# powersupply.net
KiCad netlist of a schematic drawn in Altium Designer
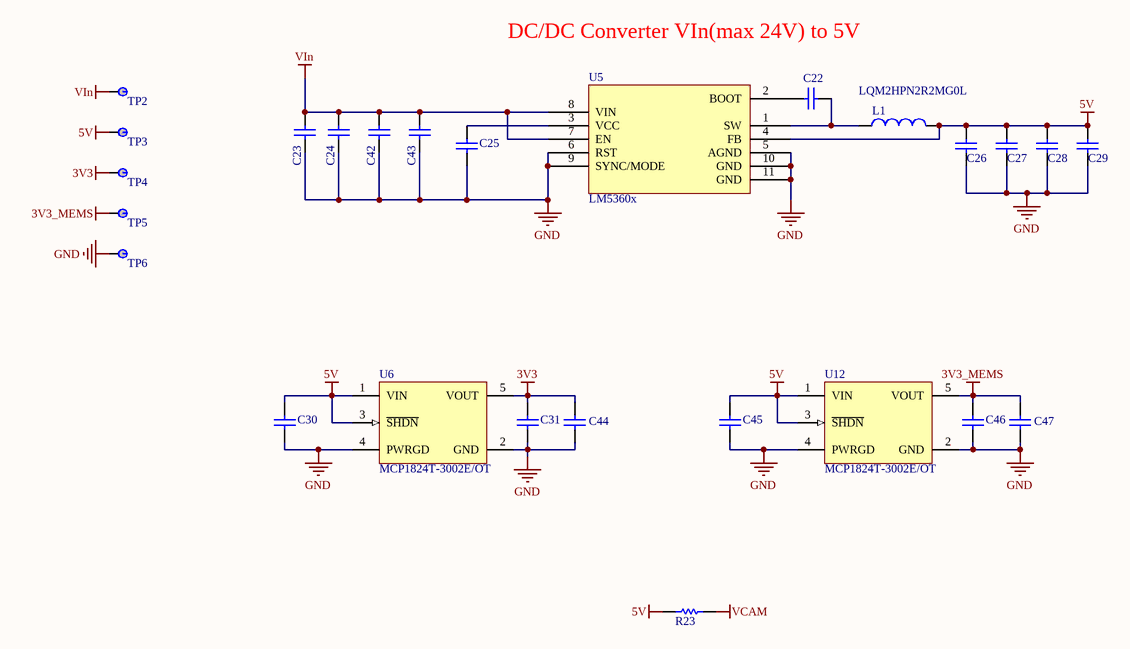
[diagram p0: powersupply.SchDoc]

(export (version "E")
  (design (tool "Eeschema 10.0.6"))
  (components
    (comp (ref "C22")
      (value "CAP 100nF 50V 0805(2012)")
      (footprint "CAPC0805(2012)100_M")
      (description "CAP 100nF 50V ±10% 0805 (2012 Metric) Thickness 1mm SMD")
      (fields (field (name "TOLERANCE") "Â±10%"))
      (libsource (lib "Altium Content Vault") (part "CAP"))
    )
    (comp (ref "C23")
      (value "CAP 4.7uF 50V 0805(2012)")
      (footprint "CAPC0805(2012)145_M")
      (description "CAP 4.7uF 50V ±20% 0805 (2012 Metric) Thickness 1.45mm SMD")
      (fields (field (name "TOLERANCE") "Â±20%"))
      (libsource (lib "Altium Content Vault") (part "CAP"))
    )
    (comp (ref "C24")
      (value "CAP 100nF 50V 0805(2012)")
      (footprint "CAPC0805(2012)100_M")
      (description "CAP 100nF 50V ±10% 0805 (2012 Metric) Thickness 1mm SMD")
      (fields (field (name "TOLERANCE") "Â±10%"))
      (libsource (lib "Altium Content Vault") (part "CAP"))
    )
    (comp (ref "C25")
      (value "CAP 1uF 6.3V 0603(1608)")
      (footprint "CAPC0603(1608)100_N")
      (description "CAP 1uF 6.3V ±10% 0603 (1608 Metric) Thickness 1mm SMD")
      (fields (field (name "TOLERANCE") "Â±10%"))
      (libsource (lib "Altium Content Vault") (part "CAP"))
    )
    (comp (ref "C26")
      (value "CAP 4.7uF 16V 0603(1608)")
      (footprint "CAPC0603(1608)100_N")
      (description "CAP 4.7uF 16V ±20% 0603 (1608 Metric) Thickness 1mm SMD")
      (fields (field (name "TOLERANCE") "Â±20%"))
      (libsource (lib "Altium Content Vault") (part "CAP"))
    )
    (comp (ref "C27")
      (value "CAP 4.7uF 16V 0603(1608)")
      (footprint "CAPC0603(1608)100_N")
      (description "CAP 4.7uF 16V ±20% 0603 (1608 Metric) Thickness 1mm SMD")
      (fields (field (name "TOLERANCE") "Â±20%"))
      (libsource (lib "Altium Content Vault") (part "CAP"))
    )
    (comp (ref "C28")
      (value "CAP 4.7uF 16V 0603(1608)")
      (footprint "CAPC0603(1608)100_N")
      (description "CAP 4.7uF 16V ±20% 0603 (1608 Metric) Thickness 1mm SMD")
      (fields (field (name "TOLERANCE") "Â±20%"))
      (libsource (lib "Altium Content Vault") (part "CAP"))
    )
    (comp (ref "C29")
      (value "CAP 4.7uF 16V 0603(1608)")
      (footprint "CAPC0603(1608)100_N")
      (description "CAP 4.7uF 16V ±20% 0603 (1608 Metric) Thickness 1mm SMD")
      (fields (field (name "TOLERANCE") "Â±20%"))
      (libsource (lib "Altium Content Vault") (part "CAP"))
    )
    (comp (ref "C30")
      (value "CAP 1uF 35V 0603(1608)")
      (footprint "CAPC0603(1608)100_L")
      (description "CAP 1uF 35V ±10% 0603 (1608 Metric) Thickness 1mm SMD")
      (fields (field (name "TOLERANCE") "Â±10%"))
      (libsource (lib "Altium Content Vault") (part "CAP"))
    )
    (comp (ref "C31")
      (value "CAP 1uF 35V 0603(1608)")
      (footprint "CAPC0603(1608)100_L")
      (description "CAP 1uF 35V ±10% 0603 (1608 Metric) Thickness 1mm SMD")
      (fields (field (name "TOLERANCE") "Â±10%"))
      (libsource (lib "Altium Content Vault") (part "CAP"))
    )
    (comp (ref "C42")
      (value "CAP 4.7uF 50V 1210(3225)")
      (footprint "CAPC1210(3225)280_L")
      (description "CAP 4.7uF 50V ±10% 1210 (3225 Metric) Thickness 2.8mm SMD")
      (fields (field (name "TOLERANCE") "Â±10%"))
      (libsource (lib "Altium Content Vault") (part "CAP"))
    )
    (comp (ref "C43")
      (value "CAP 4.7uF 50V 1210(3225)")
      (footprint "CAPC1210(3225)280_L")
      (description "CAP 4.7uF 50V ±10% 1210 (3225 Metric) Thickness 2.8mm SMD")
      (fields (field (name "TOLERANCE") "Â±10%"))
      (libsource (lib "Altium Content Vault") (part "CAP"))
    )
    (comp (ref "C44")
      (value "CAP 4.7uF 16V 0603(1608)")
      (footprint "CAPC0603(1608)100_L")
      (description "CAP 4.7uF 16V ±20% 0603 (1608 Metric) Thickness 1mm SMD")
      (fields (field (name "TOLERANCE") "Â±20%"))
      (libsource (lib "Altium Content Vault") (part "CMP-1035-02789-1"))
    )
    (comp (ref "C45")
      (value "CAP 1uF 35V 0603(1608)")
      (footprint "CAPC0603(1608)100_L")
      (description "CAP 1uF 35V ±10% 0603 (1608 Metric) Thickness 1mm SMD")
      (fields (field (name "TOLERANCE") "Â±10%"))
      (libsource (lib "Altium Content Vault") (part "CMP-1035-02743-1"))
    )
    (comp (ref "C46")
      (value "CAP 1uF 35V 0603(1608)")
      (footprint "CAPC0603(1608)100_L")
      (description "CAP 1uF 35V ±10% 0603 (1608 Metric) Thickness 1mm SMD")
      (fields (field (name "TOLERANCE") "Â±10%"))
      (libsource (lib "Altium Content Vault") (part "CMP-1035-02743-1"))
    )
    (comp (ref "C47")
      (value "CAP 4.7uF 16V 0603(1608)")
      (footprint "CAPC0603(1608)100_L")
      (description "CAP 4.7uF 16V ±20% 0603 (1608 Metric) Thickness 1mm SMD")
      (fields (field (name "TOLERANCE") "Â±20%"))
      (libsource (lib "Altium Content Vault") (part "CMP-1035-02789-1"))
    )
    (comp (ref "L1")
      (value "LQM2HPN2R2MG0L")
      (footprint "INDC2520X100X60ML20T20")
      (description "Chip Inductor, 2.2 uH, +/- 20%, -55 to 125 degC, 1008 (2520 Metric), RoHS, Tape and Reel")
      (fields (field (name "TOLERANCE") "20%"))
      (libsource (lib "Altium Content Vault") (part "IND-2"))
    )
    (comp (ref "R23")
      (value "Jumper 1206(3216)")
      (footprint "RESC1206(3216)_L")
      (description "Jumper 1206 (3216 Metric)")
      (fields (field (name "TOLERANCE") "None"))
      (libsource (lib "Altium Content Vault") (part "RES"))
    )
    (comp (ref "TP2") (value "Test Point") (footprint "TP") (libsource (lib "MyLib") (part "Test Point")))
    (comp (ref "TP3") (value "Test Point") (footprint "TP") (libsource (lib "MyLib") (part "Test Point")))
    (comp (ref "TP4") (value "Test Point") (footprint "TP") (libsource (lib "MyLib") (part "Test Point")))
    (comp (ref "TP5") (value "Test Point") (footprint "TP") (libsource (lib "MyLib") (part "Test Point")))
    (comp (ref "TP6") (value "Test Point") (footprint "TP") (libsource (lib "MyLib") (part "Test Point")))
    (comp (ref "U5") (value "LM5360x") (footprint "TI WSON-10 SD") (libsource (lib "MyLib") (part "LM5360x")))
    (comp (ref "U6")
      (value "MCP1824T-3002E/OT")
      (footprint "SOT-23-OT5_L")
      (libsource (lib "Altium Content Vault") (part "PM-LINEREG-MCP1824-IL5B"))
    )
    (comp (ref "U12")
      (value "MCP1824T-3002E/OT")
      (footprint "SOT-23-OT5_L")
      (libsource (lib "Altium Content Vault") (part "PM-LINEREG-MCP1824-IL5B"))
    )
  )
  (nets
    (net (code "1") (name "3V3") (class "Default")
      (node (ref "C31") (pin "2") (pinfunction "2_2") (pintype "passive"))
      (node (ref "C44") (pin "2") (pinfunction "2_2") (pintype "passive"))
      (node (ref "TP4") (pin "1") (pinfunction "1_1") (pintype "passive"))
      (node (ref "U6") (pin "5") (pinfunction "VOUT_5") (pintype "power_in"))
    )
    (net (code "2") (name "3V3_MEMS") (class "Default")
      (node (ref "C46") (pin "2") (pinfunction "2_2") (pintype "passive"))
      (node (ref "C47") (pin "2") (pinfunction "2_2") (pintype "passive"))
      (node (ref "TP5") (pin "1") (pinfunction "1_1") (pintype "passive"))
      (node (ref "U12") (pin "5") (pinfunction "VOUT_5") (pintype "power_in"))
    )
    (net (code "3") (name "5V") (class "Default")
      (node (ref "C26") (pin "2") (pinfunction "2_2") (pintype "passive"))
      (node (ref "C27") (pin "2") (pinfunction "2_2") (pintype "passive"))
      (node (ref "C28") (pin "2") (pinfunction "2_2") (pintype "passive"))
      (node (ref "C29") (pin "2") (pinfunction "2_2") (pintype "passive"))
      (node (ref "C30") (pin "2") (pinfunction "2_2") (pintype "passive"))
      (node (ref "C45") (pin "2") (pinfunction "2_2") (pintype "passive"))
      (node (ref "L1") (pin "2") (pinfunction "2_2") (pintype "passive"))
      (node (ref "R23") (pin "1") (pinfunction "1_1") (pintype "passive"))
      (node (ref "TP3") (pin "1") (pinfunction "1_1") (pintype "passive"))
      (node (ref "U12") (pin "1") (pinfunction "VIN_1") (pintype "power_in"))
      (node (ref "U12") (pin "3") (pinfunction "~{SHDN}_3") (pintype "input"))
      (node (ref "U5") (pin "4") (pinfunction "FB_4") (pintype "passive"))
      (node (ref "U6") (pin "1") (pinfunction "VIN_1") (pintype "power_in"))
      (node (ref "U6") (pin "3") (pinfunction "~{SHDN}_3") (pintype "input"))
    )
    (net (code "4") (name "GND") (class "Default")
      (node (ref "C23") (pin "1") (pinfunction "1_1") (pintype "passive"))
      (node (ref "C24") (pin "2") (pinfunction "2_2") (pintype "passive"))
      (node (ref "C25") (pin "1") (pinfunction "1_1") (pintype "passive"))
      (node (ref "C26") (pin "1") (pinfunction "1_1") (pintype "passive"))
      (node (ref "C27") (pin "1") (pinfunction "1_1") (pintype "passive"))
      (node (ref "C28") (pin "1") (pinfunction "1_1") (pintype "passive"))
      (node (ref "C29") (pin "1") (pinfunction "1_1") (pintype "passive"))
      (node (ref "C30") (pin "1") (pinfunction "1_1") (pintype "passive"))
      (node (ref "C31") (pin "1") (pinfunction "1_1") (pintype "passive"))
      (node (ref "C42") (pin "1") (pinfunction "1_1") (pintype "passive"))
      (node (ref "C43") (pin "1") (pinfunction "1_1") (pintype "passive"))
      (node (ref "C44") (pin "1") (pinfunction "1_1") (pintype "passive"))
      (node (ref "C45") (pin "1") (pinfunction "1_1") (pintype "passive"))
      (node (ref "C46") (pin "1") (pinfunction "1_1") (pintype "passive"))
      (node (ref "C47") (pin "1") (pinfunction "1_1") (pintype "passive"))
      (node (ref "TP6") (pin "1") (pinfunction "1_1") (pintype "passive"))
      (node (ref "U12") (pin "2") (pinfunction "GND_2") (pintype "power_in"))
      (node (ref "U12") (pin "4") (pinfunction "PWRGD_4") (pintype "power_in"))
      (node (ref "U5") (pin "10") (pinfunction "GND_10") (pintype "passive"))
      (node (ref "U5") (pin "11") (pinfunction "GND_11") (pintype "passive"))
      (node (ref "U5") (pin "5") (pinfunction "AGND_5") (pintype "passive"))
      (node (ref "U5") (pin "6") (pinfunction "RST_6") (pintype "passive"))
      (node (ref "U5") (pin "9") (pinfunction "SYNC/MODE_9") (pintype "passive"))
      (node (ref "U6") (pin "2") (pinfunction "GND_2") (pintype "power_in"))
      (node (ref "U6") (pin "4") (pinfunction "PWRGD_4") (pintype "power_in"))
    )
    (net (code "5") (name "Net-(U5-BOOT)") (class "Default")
      (node (ref "C22") (pin "1") (pinfunction "1_1") (pintype "passive"))
      (node (ref "U5") (pin "2") (pinfunction "BOOT_2") (pintype "passive"))
    )
    (net (code "6") (name "Net-(U5-SW)") (class "Default")
      (node (ref "C22") (pin "2") (pinfunction "2_2") (pintype "passive"))
      (node (ref "L1") (pin "1") (pinfunction "1_1") (pintype "passive"))
      (node (ref "U5") (pin "1") (pinfunction "SW_1") (pintype "passive"))
    )
    (net (code "7") (name "Net-(U5-VCC)") (class "Default")
      (node (ref "C25") (pin "2") (pinfunction "2_2") (pintype "passive"))
      (node (ref "U5") (pin "3") (pinfunction "VCC_3") (pintype "passive"))
    )
    (net (code "8") (name "VCAM") (class "Default")
      (node (ref "R23") (pin "2") (pinfunction "2_2") (pintype "passive"))
    )
    (net (code "9") (name "VIn") (class "Default")
      (node (ref "C23") (pin "2") (pinfunction "2_2") (pintype "passive"))
      (node (ref "C24") (pin "1") (pinfunction "1_1") (pintype "passive"))
      (node (ref "C42") (pin "2") (pinfunction "2_2") (pintype "passive"))
      (node (ref "C43") (pin "2") (pinfunction "2_2") (pintype "passive"))
      (node (ref "TP2") (pin "1") (pinfunction "1_1") (pintype "passive"))
      (node (ref "U5") (pin "7") (pinfunction "EN_7") (pintype "passive"))
      (node (ref "U5") (pin "8") (pinfunction "VIN_8") (pintype "passive"))
    )
  )
)
